# WR_clocks.net
KiCad netlist of a schematic drawn in Altium Designer
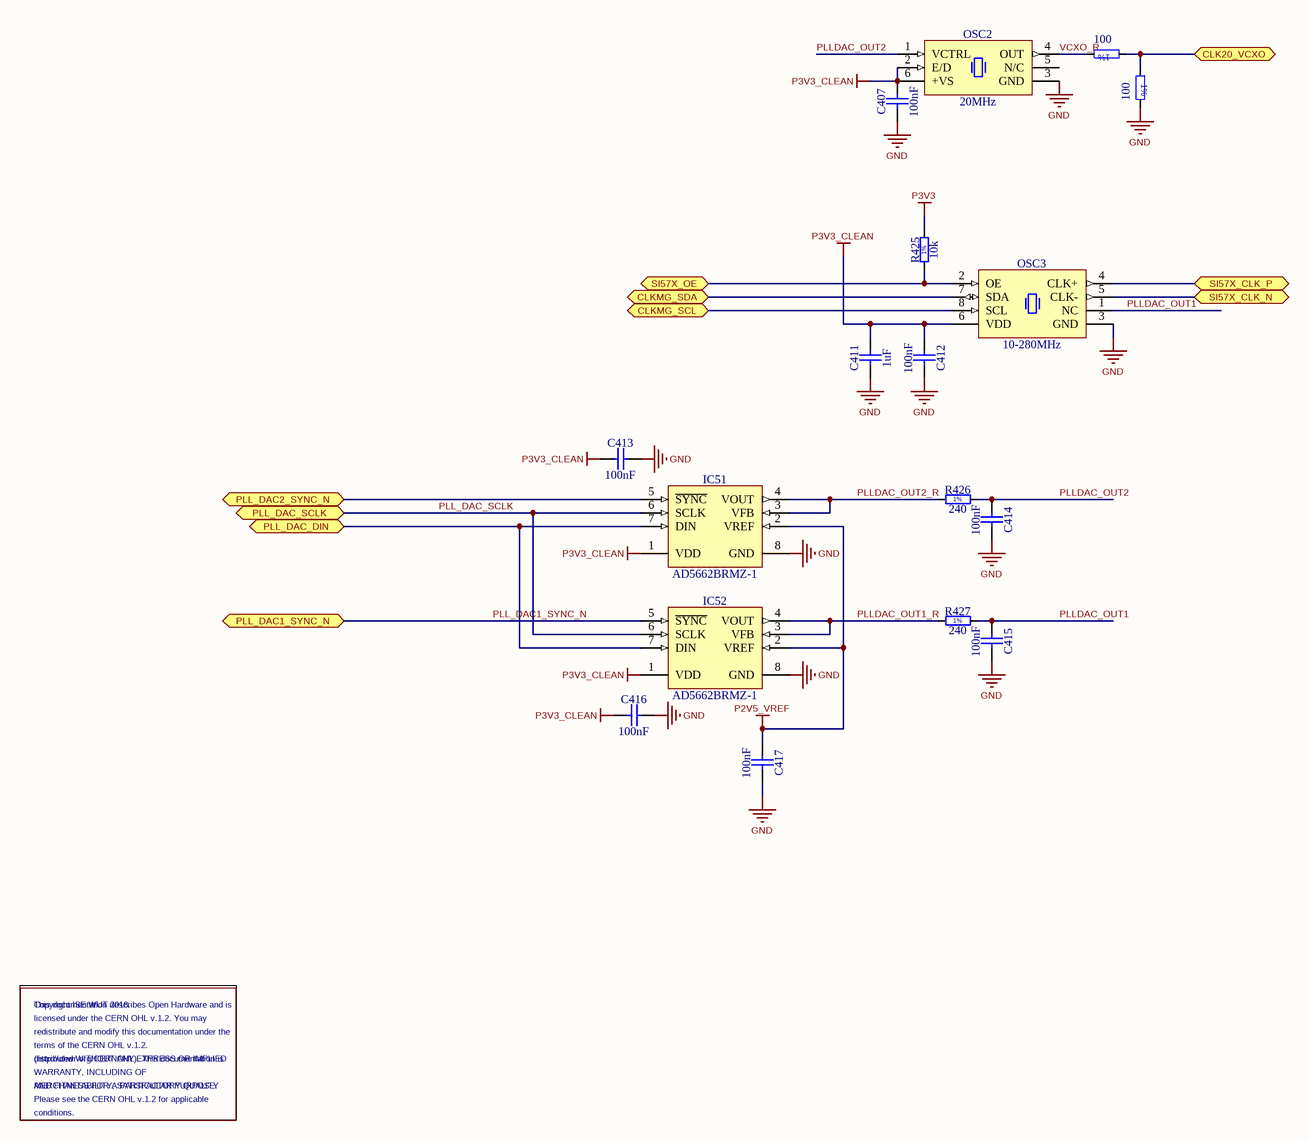
[diagram p0: WR_clocks.SchDoc]

(export (version "E")
  (design (tool "Eeschema 10.0.6"))
  (components
    (comp (ref "7")
      (value "100")
      (fields
        (field (name "$$NOTCOMMONPROPERTY_GENERAL PART NUMBER") "R0402_100R_1%_0.1W_100PPM")
        (field (name "$$NOTCOMMONPROPERTY_MANUFACTURER1 PART NUMBER") "ERJ2RKF1000X")
        (field (name "MANUFACTURER PART NUMBER") "R0402_100R_1%_0.1W_100PPM_50V")
      )
      (libsource (lib "altium-import") (part "root_2__*"))
    )
    (comp (ref "8")
      (value "100")
      (fields
        (field (name "$$NOTCOMMONPROPERTY_GENERAL PART NUMBER") "R0402_100R_1%_0.1W_100PPM")
        (field (name "$$NOTCOMMONPROPERTY_MANUFACTURER1 PART NUMBER") "ERJ2RKF1000X")
        (field (name "MANUFACTURER PART NUMBER") "R0402_100R_1%_0.1W_100PPM_50V")
      )
      (libsource (lib "altium-import") (part "root_3__*"))
    )
    (comp (ref "C407")
      (value "100nF")
      (footprint "CAPC0603X33N")
      (description "Non-polarised capacitor")
      (fields
        (field (name "MANUFACTURER PART NUMBER") "CC0201_100NF_6.3V_10%_X5R")
        (field (name "MANUFACTURER") "GENERIC")
        (field (name "AUTHOR") "CERN DEM JLC")
      )
      (libsource (lib "Capacitors") (part "Capacitor - non polarized"))
    )
    (comp (ref "C411")
      (value "1uF")
      (footprint "CAPC1005X55N")
      (description "Non-polarised capacitor")
      (fields
        (field (name "MANUFACTURER PART NUMBER") "CC0402_1UF_16V_10%_X5R")
        (field (name "MANUFACTURER") "GENERIC")
        (field (name "AUTHOR") "CERN DEM JLC")
      )
      (libsource (lib "Capacitors") (part "Capacitor - non polarized"))
    )
    (comp (ref "C412")
      (value "100nF")
      (footprint "CAPC0603X33N")
      (description "Non-polarised capacitor")
      (fields
        (field (name "MANUFACTURER PART NUMBER") "CC0201_100NF_6.3V_10%_X5R")
        (field (name "MANUFACTURER") "GENERIC")
        (field (name "AUTHOR") "CERN DEM JLC")
      )
      (libsource (lib "Capacitors") (part "Capacitor - non polarized"))
    )
    (comp (ref "C413")
      (value "100nF")
      (footprint "CAPC0603X33N")
      (description "Non-polarised capacitor")
      (fields
        (field (name "MANUFACTURER PART NUMBER") "CC0201_100NF_6.3V_10%_X5R")
        (field (name "MANUFACTURER") "GENERIC")
        (field (name "AUTHOR") "CERN DEM JLC")
      )
      (libsource (lib "Capacitors") (part "Capacitor - non polarized"))
    )
    (comp (ref "C414")
      (value "100nF")
      (footprint "CAPC0603X33N")
      (description "Non-polarised capacitor")
      (fields
        (field (name "MANUFACTURER PART NUMBER") "CC0201_100NF_6.3V_10%_X5R")
        (field (name "MANUFACTURER") "GENERIC")
        (field (name "AUTHOR") "CERN DEM JLC")
      )
      (libsource (lib "Capacitors") (part "Capacitor - non polarized"))
    )
    (comp (ref "C415")
      (value "100nF")
      (footprint "CAPC0603X33N")
      (description "Non-polarised capacitor")
      (fields
        (field (name "MANUFACTURER PART NUMBER") "CC0201_100NF_6.3V_10%_X5R")
        (field (name "MANUFACTURER") "GENERIC")
        (field (name "AUTHOR") "CERN DEM JLC")
      )
      (libsource (lib "Capacitors") (part "Capacitor - non polarized"))
    )
    (comp (ref "C416")
      (value "100nF")
      (footprint "CAPC0603X33N")
      (description "Non-polarised capacitor")
      (fields
        (field (name "MANUFACTURER PART NUMBER") "CC0201_100NF_6.3V_10%_X5R")
        (field (name "MANUFACTURER") "GENERIC")
        (field (name "AUTHOR") "CERN DEM JLC")
      )
      (libsource (lib "Capacitors") (part "Capacitor - non polarized"))
    )
    (comp (ref "C417")
      (value "100nF")
      (footprint "CAPC0603X33N")
      (description "Non-polarised capacitor")
      (fields
        (field (name "MANUFACTURER PART NUMBER") "CC0201_100NF_6.3V_10%_X5R")
        (field (name "MANUFACTURER") "GENERIC")
        (field (name "AUTHOR") "CERN DEM JLC")
      )
      (libsource (lib "Capacitors") (part "Capacitor - non polarized"))
    )
    (comp (ref "IC51")
      (value "AD5662BRMZ-1")
      (footprint "SOP65P490X110-8N")
      (description "2.7V to 5.5V, 250uA, Rail-to-Rail Output 16-Bit nanoDAC")
      (fields (field (name "MANUFACTURER") "ANALOG DEVICES") (field (name "AUTHOR") "CERN DEM JLC"))
      (libsource (lib "ICs And Semiconductors") (part "AD5662"))
    )
    (comp (ref "IC52")
      (value "AD5662BRMZ-1")
      (footprint "SOP65P490X110-8N")
      (description "2.7V to 5.5V, 250uA, Rail-to-Rail Output 16-Bit nanoDAC")
      (fields (field (name "MANUFACTURER") "ANALOG DEVICES") (field (name "AUTHOR") "CERN DEM JLC"))
      (libsource (lib "ICs And Semiconductors") (part "AD5662"))
    )
    (comp (ref "OSC2")
      (value "20MHz")
      (footprint "OSC_IQD_CFPV-45")
      (description "3.3V ±100ppm 15pF HCMOS Tri-State Surface Mount Voltage Controlled Oscillator VCXO (CFPV-45 Serie)")
      (fields
        (field (name "PART NUMBER") "OSC_20MHZ_IQD_LFVCXO026156")
        (field (name "MANUFACTURER") "IQD FREQUENCY PRODUCTS")
        (field (name "AUTHOR") "CERN DEM JLC")
      )
      (libsource (lib "ICs And Semiconductors") (part "Oscillator IQD_CFPV-45"))
    )
    (comp (ref "OSC3")
      (value "10-280MHz")
      (footprint "OSC_SILICON-LAB_SI570")
      (description "Any-Rate I2C Programmable XO Oscillator Si570 Serie")
      (fields
        (field (name "MANUFACTURER PART NUMBER") "570BBC000121DG")
        (field (name "MANUFACTURER") "SILICON LABS")
        (field (name "AUTHOR") "CERN DEM JLC")
      )
      (libsource (lib "ICs And Semiconductors") (part "Oscillator SILICON-LAB_Si570"))
    )
    (comp (ref "R425")
      (value "10k")
      (footprint "RESC1005X40N")
      (description "Resistor - 1%")
      (fields
        (field (name "MANUFACTURER PART NUMBER") "R0402_10K_1%_0.0625W_100PPM")
        (field (name "MANUFACTURER") "GENERIC")
        (field (name "AUTHOR") "CERN DEM JLC")
      )
      (libsource (lib "Resistors") (part "Resistor - 1%"))
    )
    (comp (ref "R426")
      (value "240")
      (footprint "RESC1005X40N")
      (description "Resistor - 1%")
      (fields
        (field (name "MANUFACTURER PART NUMBER") "R0402_240R_1%_0.0625W_100PPM")
        (field (name "MANUFACTURER") "GENERIC")
        (field (name "AUTHOR") "CERN DEM JLC")
      )
      (libsource (lib "Resistors") (part "Resistor - 1%"))
    )
    (comp (ref "R427")
      (value "240")
      (footprint "RESC1005X40N")
      (description "Resistor - 1%")
      (fields
        (field (name "MANUFACTURER PART NUMBER") "R0402_240R_1%_0.0625W_100PPM")
        (field (name "MANUFACTURER") "GENERIC")
        (field (name "AUTHOR") "CERN DEM JLC")
      )
      (libsource (lib "Resistors") (part "Resistor - 1%"))
    )
  )
  (nets
    (net (code "1") (name "/CLK20_VCXO") (class "Default")
      (node (ref "7") (pin "1") (pinfunction "1_1") (pintype "passive"))
      (node (ref "8") (pin "1") (pinfunction "1_1") (pintype "passive"))
    )
    (net (code "2") (name "/CLKMG_SCL") (class "Default")
      (node (ref "OSC3") (pin "8") (pinfunction "SCL_8") (pintype "input"))
    )
    (net (code "3") (name "/CLKMG_SDA") (class "Default")
      (node (ref "OSC3") (pin "7") (pinfunction "SDA_7") (pintype "bidirectional"))
    )
    (net (code "4") (name "/PLLDAC_OUT1") (class "Default")
      (node (ref "C415") (pin "1") (pinfunction "1_1") (pintype "passive"))
      (node (ref "OSC3") (pin "1") (pinfunction "NC_1") (pintype "passive"))
      (node (ref "R427") (pin "2") (pinfunction "2_2") (pintype "passive"))
    )
    (net (code "5") (name "/PLLDAC_OUT1_R") (class "Default")
      (node (ref "IC52") (pin "3") (pinfunction "VFB_3") (pintype "input"))
      (node (ref "IC52") (pin "4") (pinfunction "VOUT_4") (pintype "output"))
      (node (ref "R427") (pin "1") (pinfunction "1_1") (pintype "passive"))
    )
    (net (code "6") (name "/PLLDAC_OUT2") (class "Default")
      (node (ref "C414") (pin "1") (pinfunction "1_1") (pintype "passive"))
      (node (ref "OSC2") (pin "1") (pinfunction "VCTRL_1") (pintype "input"))
      (node (ref "R426") (pin "2") (pinfunction "2_2") (pintype "passive"))
    )
    (net (code "7") (name "/PLLDAC_OUT2_R") (class "Default")
      (node (ref "IC51") (pin "3") (pinfunction "VFB_3") (pintype "input"))
      (node (ref "IC51") (pin "4") (pinfunction "VOUT_4") (pintype "output"))
      (node (ref "R426") (pin "1") (pinfunction "1_1") (pintype "passive"))
    )
    (net (code "8") (name "/PLL_DAC1_SYNC_N") (class "Default")
      (node (ref "IC52") (pin "5") (pinfunction "~{SYNC}_5") (pintype "input"))
    )
    (net (code "9") (name "/PLL_DAC2_SYNC_N") (class "Default")
      (node (ref "IC51") (pin "5") (pinfunction "~{SYNC}_5") (pintype "input"))
    )
    (net (code "10") (name "/PLL_DAC_DIN") (class "Default")
      (node (ref "IC51") (pin "7") (pinfunction "DIN_7") (pintype "input"))
      (node (ref "IC52") (pin "7") (pinfunction "DIN_7") (pintype "input"))
    )
    (net (code "11") (name "/PLL_DAC_SCLK") (class "Default")
      (node (ref "IC51") (pin "6") (pinfunction "SCLK_6") (pintype "input"))
      (node (ref "IC52") (pin "6") (pinfunction "SCLK_6") (pintype "input"))
    )
    (net (code "12") (name "/SI57X_CLK_N") (class "Default")
      (node (ref "OSC3") (pin "5") (pinfunction "CLK-_5") (pintype "output"))
    )
    (net (code "13") (name "/SI57X_CLK_P") (class "Default")
      (node (ref "OSC3") (pin "4") (pinfunction "CLK+_4") (pintype "output"))
    )
    (net (code "14") (name "/SI57X_OE") (class "Default")
      (node (ref "OSC3") (pin "2") (pinfunction "OE_2") (pintype "input"))
      (node (ref "R425") (pin "1") (pinfunction "1_1") (pintype "passive"))
    )
    (net (code "15") (name "/VCXO_R") (class "Default")
      (node (ref "7") (pin "2") (pinfunction "2_2") (pintype "passive"))
      (node (ref "OSC2") (pin "4") (pinfunction "OUT_4") (pintype "output"))
    )
    (net (code "16") (name "GND") (class "Default")
      (node (ref "8") (pin "2") (pinfunction "2_2") (pintype "passive"))
      (node (ref "C407") (pin "1") (pinfunction "1_1") (pintype "passive"))
      (node (ref "C411") (pin "1") (pinfunction "1_1") (pintype "passive"))
      (node (ref "C412") (pin "2") (pinfunction "2_2") (pintype "passive"))
      (node (ref "C413") (pin "2") (pinfunction "2_2") (pintype "passive"))
      (node (ref "C414") (pin "2") (pinfunction "2_2") (pintype "passive"))
      (node (ref "C415") (pin "2") (pinfunction "2_2") (pintype "passive"))
      (node (ref "C416") (pin "2") (pinfunction "2_2") (pintype "passive"))
      (node (ref "C417") (pin "2") (pinfunction "2_2") (pintype "passive"))
      (node (ref "IC51") (pin "8") (pinfunction "GND_8") (pintype "power_in"))
      (node (ref "IC52") (pin "8") (pinfunction "GND_8") (pintype "power_in"))
      (node (ref "OSC2") (pin "3") (pinfunction "GND_3") (pintype "power_in"))
      (node (ref "OSC3") (pin "3") (pinfunction "GND_3") (pintype "power_in"))
    )
    (net (code "17") (name "P2V5_VREF") (class "Default")
      (node (ref "C417") (pin "1") (pinfunction "1_1") (pintype "passive"))
      (node (ref "IC51") (pin "2") (pinfunction "VREF_2") (pintype "input"))
      (node (ref "IC52") (pin "2") (pinfunction "VREF_2") (pintype "input"))
    )
    (net (code "18") (name "P3V3") (class "Default")
      (node (ref "R425") (pin "2") (pinfunction "2_2") (pintype "passive"))
    )
    (net (code "19") (name "P3V3_CLEAN") (class "Default")
      (node (ref "C407") (pin "2") (pinfunction "2_2") (pintype "passive"))
      (node (ref "C411") (pin "2") (pinfunction "2_2") (pintype "passive"))
      (node (ref "C412") (pin "1") (pinfunction "1_1") (pintype "passive"))
      (node (ref "C413") (pin "1") (pinfunction "1_1") (pintype "passive"))
      (node (ref "C416") (pin "1") (pinfunction "1_1") (pintype "passive"))
      (node (ref "IC51") (pin "1") (pinfunction "VDD_1") (pintype "power_in"))
      (node (ref "IC52") (pin "1") (pinfunction "VDD_1") (pintype "power_in"))
      (node (ref "OSC2") (pin "2") (pinfunction "E/D_2") (pintype "input"))
      (node (ref "OSC2") (pin "6") (pinfunction "+VS_6") (pintype "power_in"))
      (node (ref "OSC3") (pin "6") (pinfunction "VDD_6") (pintype "power_in"))
    )
    (net (code "20") (name "unconnected-(OSC2-N{slash}C-Pad5)") (class "Default")
      (node (ref "OSC2") (pin "5") (pinfunction "N/C_5") (pintype "passive"))
    )
  )
)
